# DS18B20exampleSerial.net
KiCad netlist of a schematic drawn in EAGLE
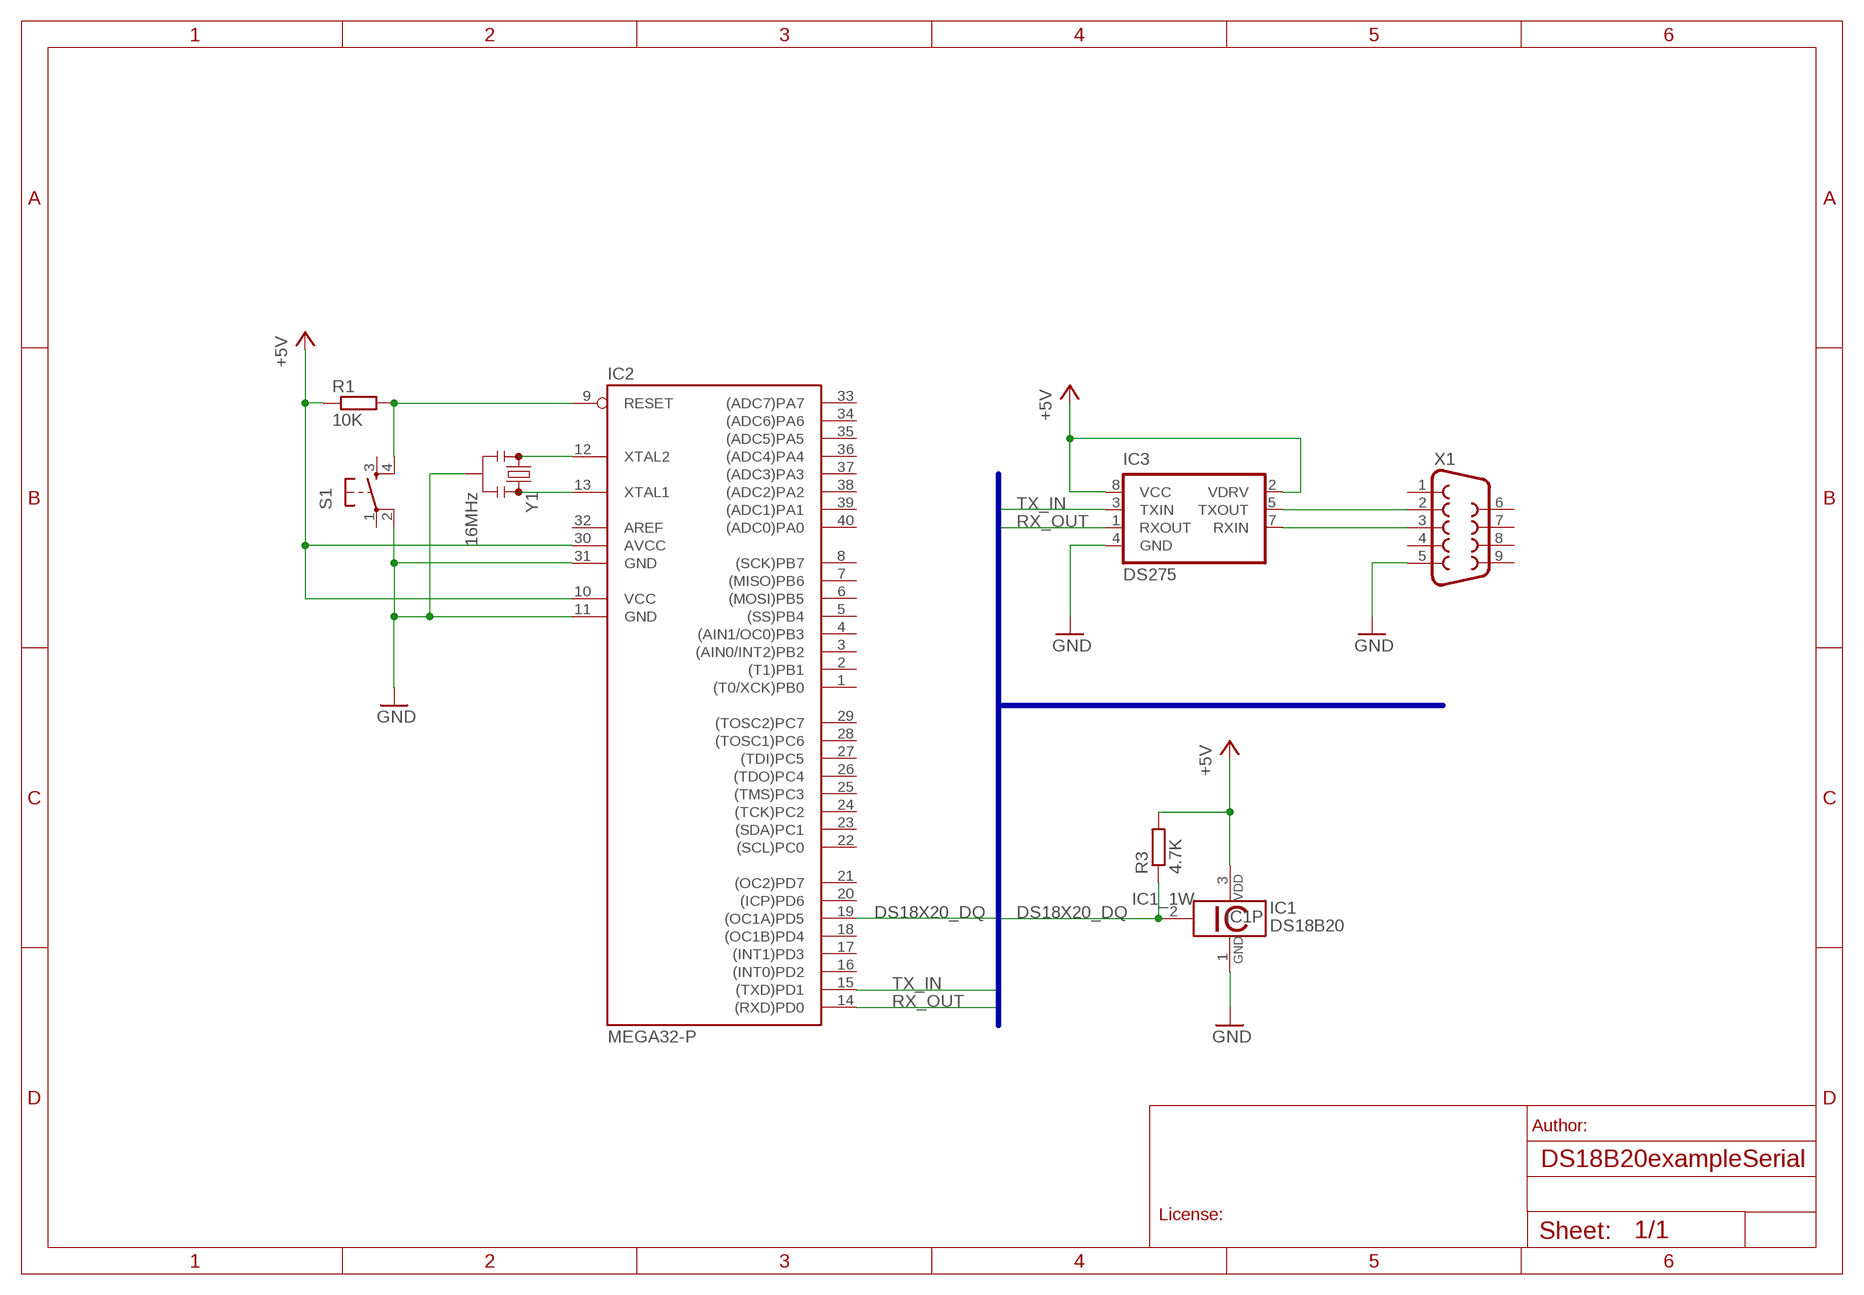
[diagram p0: schematic, sheet 1]

(export (version "E")
  (design (tool "Eeschema 10.0.6"))
  (components
    (comp (ref "IC1")
      (value "DS18B20")
      (footprint "eagle-import:TO92-")
      (libsource (lib "eagle-import") (part "DS18B20"))
    )
    (comp (ref "IC2")
      (value "MEGA32-P")
      (footprint "eagle-import:DIL40")
      (fields (field (name "MPN") "ATMEGA32-16PU"))
      (libsource (lib "eagle-import") (part "MEGA32-P"))
    )
    (comp (ref "IC3")
      (value "DS275")
      (footprint "eagle-import:DIL08")
      (fields (field (name "MPN") "DS275+"))
      (libsource (lib "eagle-import") (part "DS275"))
    )
    (comp (ref "R1")
      (value "10K")
      (footprint "eagle-import:0204_7")
      (libsource (lib "eagle-import") (part "R-EU_0204/7"))
    )
    (comp (ref "R3")
      (value "4.7K")
      (footprint "eagle-import:0204_7")
      (libsource (lib "eagle-import") (part "R-EU_0204/7"))
    )
    (comp (ref "S1")
      (value "TAC_SWITCHPTH")
      (footprint "eagle-import:TACTILE-PTH")
      (libsource (lib "eagle-import") (part "TAC_SWITCHPTH"))
    )
    (comp (ref "X1")
      (value "F09HP")
      (footprint "eagle-import:F09HP")
      (libsource (lib "eagle-import") (part "F09HP"))
    )
    (comp (ref "Y1")
      (value "16MHz")
      (footprint "eagle-import:RESONATOR-PTH")
      (libsource (lib "eagle-import") (part "RESONATORPTH"))
    )
  )
  (nets
    (net (code "1") (name "+5V") (class "Default")
      (node (ref "IC1") (pin "3") (pinfunction "VDD_3") (pintype "power_in"))
      (node (ref "IC2") (pin "10") (pinfunction "VCC_10") (pintype "power_in"))
      (node (ref "IC2") (pin "30") (pinfunction "AVCC_30") (pintype "power_in"))
      (node (ref "IC3") (pin "2") (pinfunction "VDRV_2") (pintype "input"))
      (node (ref "IC3") (pin "8") (pinfunction "VCC_8") (pintype "power_in"))
      (node (ref "R1") (pin "1") (pinfunction "1_1") (pintype "passive"))
      (node (ref "R3") (pin "2") (pinfunction "2_2") (pintype "passive"))
    )
    (net (code "2") (name "/DS18X20_DQ") (class "Default")
      (node (ref "IC1") (pin "2") (pinfunction "1W_2") (pintype "power_in"))
      (node (ref "IC2") (pin "19") (pinfunction "(OC1A)PD5_19") (pintype "bidirectional"))
      (node (ref "R3") (pin "1") (pinfunction "1_1") (pintype "passive"))
    )
    (net (code "3") (name "/RX_OUT") (class "Default")
      (node (ref "IC2") (pin "14") (pinfunction "(RXD)PD0_14") (pintype "bidirectional"))
      (node (ref "IC3") (pin "1") (pinfunction "RXOUT_1") (pintype "output"))
    )
    (net (code "4") (name "/TX_IN") (class "Default")
      (node (ref "IC2") (pin "15") (pinfunction "(TXD)PD1_15") (pintype "bidirectional"))
      (node (ref "IC3") (pin "3") (pinfunction "TXIN_3") (pintype "input"))
    )
    (net (code "5") (name "GND") (class "Default")
      (node (ref "IC1") (pin "1") (pinfunction "GND_1") (pintype "power_in"))
      (node (ref "IC2") (pin "11") (pinfunction "GND_11") (pintype "power_in"))
      (node (ref "IC2") (pin "31") (pinfunction "GND_31") (pintype "power_in"))
      (node (ref "IC3") (pin "4") (pinfunction "GND_4") (pintype "power_in"))
      (node (ref "S1") (pin "2") (pinfunction "2_2") (pintype "passive"))
      (node (ref "X1") (pin "5") (pinfunction "5_5") (pintype "passive"))
      (node (ref "Y1") (pin "2") (pinfunction "2_2") (pintype "passive"))
    )
    (net (code "6") (name "Net-(IC2-RESET)") (class "Default")
      (node (ref "IC2") (pin "9") (pinfunction "RESET_9") (pintype "input"))
      (node (ref "R1") (pin "2") (pinfunction "2_2") (pintype "passive"))
      (node (ref "S1") (pin "4") (pinfunction "4_4") (pintype "passive"))
    )
    (net (code "7") (name "Net-(IC2-XTAL1)") (class "Default")
      (node (ref "IC2") (pin "13") (pinfunction "XTAL1_13") (pintype "bidirectional"))
      (node (ref "Y1") (pin "3") (pinfunction "3_3") (pintype "passive"))
    )
    (net (code "8") (name "Net-(IC2-XTAL2)") (class "Default")
      (node (ref "IC2") (pin "12") (pinfunction "XTAL2_12") (pintype "bidirectional"))
      (node (ref "Y1") (pin "1") (pinfunction "1_1") (pintype "passive"))
    )
    (net (code "9") (name "Net-(IC3-RXIN)") (class "Default")
      (node (ref "IC3") (pin "7") (pinfunction "RXIN_7") (pintype "input"))
      (node (ref "X1") (pin "3") (pinfunction "3_3") (pintype "passive"))
    )
    (net (code "10") (name "Net-(IC3-TXOUT)") (class "Default")
      (node (ref "IC3") (pin "5") (pinfunction "TXOUT_5") (pintype "output"))
      (node (ref "X1") (pin "2") (pinfunction "2_2") (pintype "passive"))
    )
    (net (code "11") (name "unconnected-(IC2-(ADC0)PA0-Pad40)") (class "Default")
      (node (ref "IC2") (pin "40") (pinfunction "(ADC0)PA0_40") (pintype "bidirectional"))
    )
    (net (code "12") (name "unconnected-(IC2-(ADC1)PA1-Pad39)") (class "Default")
      (node (ref "IC2") (pin "39") (pinfunction "(ADC1)PA1_39") (pintype "bidirectional"))
    )
    (net (code "13") (name "unconnected-(IC2-(ADC2)PA2-Pad38)") (class "Default")
      (node (ref "IC2") (pin "38") (pinfunction "(ADC2)PA2_38") (pintype "bidirectional"))
    )
    (net (code "14") (name "unconnected-(IC2-(ADC3)PA3-Pad37)") (class "Default")
      (node (ref "IC2") (pin "37") (pinfunction "(ADC3)PA3_37") (pintype "bidirectional"))
    )
    (net (code "15") (name "unconnected-(IC2-(ADC4)PA4-Pad36)") (class "Default")
      (node (ref "IC2") (pin "36") (pinfunction "(ADC4)PA4_36") (pintype "bidirectional"))
    )
    (net (code "16") (name "unconnected-(IC2-(ADC5)PA5-Pad35)") (class "Default")
      (node (ref "IC2") (pin "35") (pinfunction "(ADC5)PA5_35") (pintype "bidirectional"))
    )
    (net (code "17") (name "unconnected-(IC2-(ADC6)PA6-Pad34)") (class "Default")
      (node (ref "IC2") (pin "34") (pinfunction "(ADC6)PA6_34") (pintype "bidirectional"))
    )
    (net (code "18") (name "unconnected-(IC2-(ADC7)PA7-Pad33)") (class "Default")
      (node (ref "IC2") (pin "33") (pinfunction "(ADC7)PA7_33") (pintype "bidirectional"))
    )
    (net (code "19") (name "unconnected-(IC2-(AIN0{slash}INT2)PB2-Pad3)") (class "Default")
      (node (ref "IC2") (pin "3") (pinfunction "(AIN0/INT2)PB2_3") (pintype "bidirectional"))
    )
    (net (code "20") (name "unconnected-(IC2-(AIN1{slash}OC0)PB3-Pad4)") (class "Default")
      (node (ref "IC2") (pin "4") (pinfunction "(AIN1/OC0)PB3_4") (pintype "bidirectional"))
    )
    (net (code "21") (name "unconnected-(IC2-(ICP)PD6-Pad20)") (class "Default")
      (node (ref "IC2") (pin "20") (pinfunction "(ICP)PD6_20") (pintype "bidirectional"))
    )
    (net (code "22") (name "unconnected-(IC2-(INT0)PD2-Pad16)") (class "Default")
      (node (ref "IC2") (pin "16") (pinfunction "(INT0)PD2_16") (pintype "bidirectional"))
    )
    (net (code "23") (name "unconnected-(IC2-(INT1)PD3-Pad17)") (class "Default")
      (node (ref "IC2") (pin "17") (pinfunction "(INT1)PD3_17") (pintype "bidirectional"))
    )
    (net (code "24") (name "unconnected-(IC2-(MISO)PB6-Pad7)") (class "Default")
      (node (ref "IC2") (pin "7") (pinfunction "(MISO)PB6_7") (pintype "bidirectional"))
    )
    (net (code "25") (name "unconnected-(IC2-(MOSI)PB5-Pad6)") (class "Default")
      (node (ref "IC2") (pin "6") (pinfunction "(MOSI)PB5_6") (pintype "bidirectional"))
    )
    (net (code "26") (name "unconnected-(IC2-(OC1B)PD4-Pad18)") (class "Default")
      (node (ref "IC2") (pin "18") (pinfunction "(OC1B)PD4_18") (pintype "bidirectional"))
    )
    (net (code "27") (name "unconnected-(IC2-(OC2)PD7-Pad21)") (class "Default")
      (node (ref "IC2") (pin "21") (pinfunction "(OC2)PD7_21") (pintype "bidirectional"))
    )
    (net (code "28") (name "unconnected-(IC2-(SCK)PB7-Pad8)") (class "Default")
      (node (ref "IC2") (pin "8") (pinfunction "(SCK)PB7_8") (pintype "bidirectional"))
    )
    (net (code "29") (name "unconnected-(IC2-(SCL)PC0-Pad22)") (class "Default")
      (node (ref "IC2") (pin "22") (pinfunction "(SCL)PC0_22") (pintype "bidirectional"))
    )
    (net (code "30") (name "unconnected-(IC2-(SDA)PC1-Pad23)") (class "Default")
      (node (ref "IC2") (pin "23") (pinfunction "(SDA)PC1_23") (pintype "bidirectional"))
    )
    (net (code "31") (name "unconnected-(IC2-(SS)PB4-Pad5)") (class "Default")
      (node (ref "IC2") (pin "5") (pinfunction "(SS)PB4_5") (pintype "bidirectional"))
    )
    (net (code "32") (name "unconnected-(IC2-(T0{slash}XCK)PB0-Pad1)") (class "Default")
      (node (ref "IC2") (pin "1") (pinfunction "(T0/XCK)PB0_1") (pintype "bidirectional"))
    )
    (net (code "33") (name "unconnected-(IC2-(T1)PB1-Pad2)") (class "Default")
      (node (ref "IC2") (pin "2") (pinfunction "(T1)PB1_2") (pintype "bidirectional"))
    )
    (net (code "34") (name "unconnected-(IC2-(TCK)PC2-Pad24)") (class "Default")
      (node (ref "IC2") (pin "24") (pinfunction "(TCK)PC2_24") (pintype "bidirectional"))
    )
    (net (code "35") (name "unconnected-(IC2-(TDI)PC5-Pad27)") (class "Default")
      (node (ref "IC2") (pin "27") (pinfunction "(TDI)PC5_27") (pintype "bidirectional"))
    )
    (net (code "36") (name "unconnected-(IC2-(TDO)PC4-Pad26)") (class "Default")
      (node (ref "IC2") (pin "26") (pinfunction "(TDO)PC4_26") (pintype "bidirectional"))
    )
    (net (code "37") (name "unconnected-(IC2-(TMS)PC3-Pad25)") (class "Default")
      (node (ref "IC2") (pin "25") (pinfunction "(TMS)PC3_25") (pintype "bidirectional"))
    )
    (net (code "38") (name "unconnected-(IC2-(TOSC1)PC6-Pad28)") (class "Default")
      (node (ref "IC2") (pin "28") (pinfunction "(TOSC1)PC6_28") (pintype "bidirectional"))
    )
    (net (code "39") (name "unconnected-(IC2-(TOSC2)PC7-Pad29)") (class "Default")
      (node (ref "IC2") (pin "29") (pinfunction "(TOSC2)PC7_29") (pintype "bidirectional"))
    )
    (net (code "40") (name "unconnected-(IC2-AREF-Pad32)") (class "Default")
      (node (ref "IC2") (pin "32") (pinfunction "AREF_32") (pintype "passive"))
    )
    (net (code "41") (name "unconnected-(S1-Pad1)") (class "Default")
      (node (ref "S1") (pin "1") (pinfunction "1_1") (pintype "passive"))
    )
    (net (code "42") (name "unconnected-(S1-Pad3)") (class "Default")
      (node (ref "S1") (pin "3") (pinfunction "3_3") (pintype "passive"))
    )
    (net (code "43") (name "unconnected-(X1-Pad1)") (class "Default")
      (node (ref "X1") (pin "1") (pinfunction "1_1") (pintype "passive"))
    )
    (net (code "44") (name "unconnected-(X1-Pad4)") (class "Default")
      (node (ref "X1") (pin "4") (pinfunction "4_4") (pintype "passive"))
    )
    (net (code "45") (name "unconnected-(X1-Pad6)") (class "Default")
      (node (ref "X1") (pin "6") (pinfunction "6_6") (pintype "passive"))
    )
    (net (code "46") (name "unconnected-(X1-Pad7)") (class "Default")
      (node (ref "X1") (pin "7") (pinfunction "7_7") (pintype "passive"))
    )
    (net (code "47") (name "unconnected-(X1-Pad8)") (class "Default")
      (node (ref "X1") (pin "8") (pinfunction "8_8") (pintype "passive"))
    )
    (net (code "48") (name "unconnected-(X1-Pad9)") (class "Default")
      (node (ref "X1") (pin "9") (pinfunction "9_9") (pintype "passive"))
    )
  )
)
